# DressCode.net
KiCad netlist of a schematic drawn in EAGLE
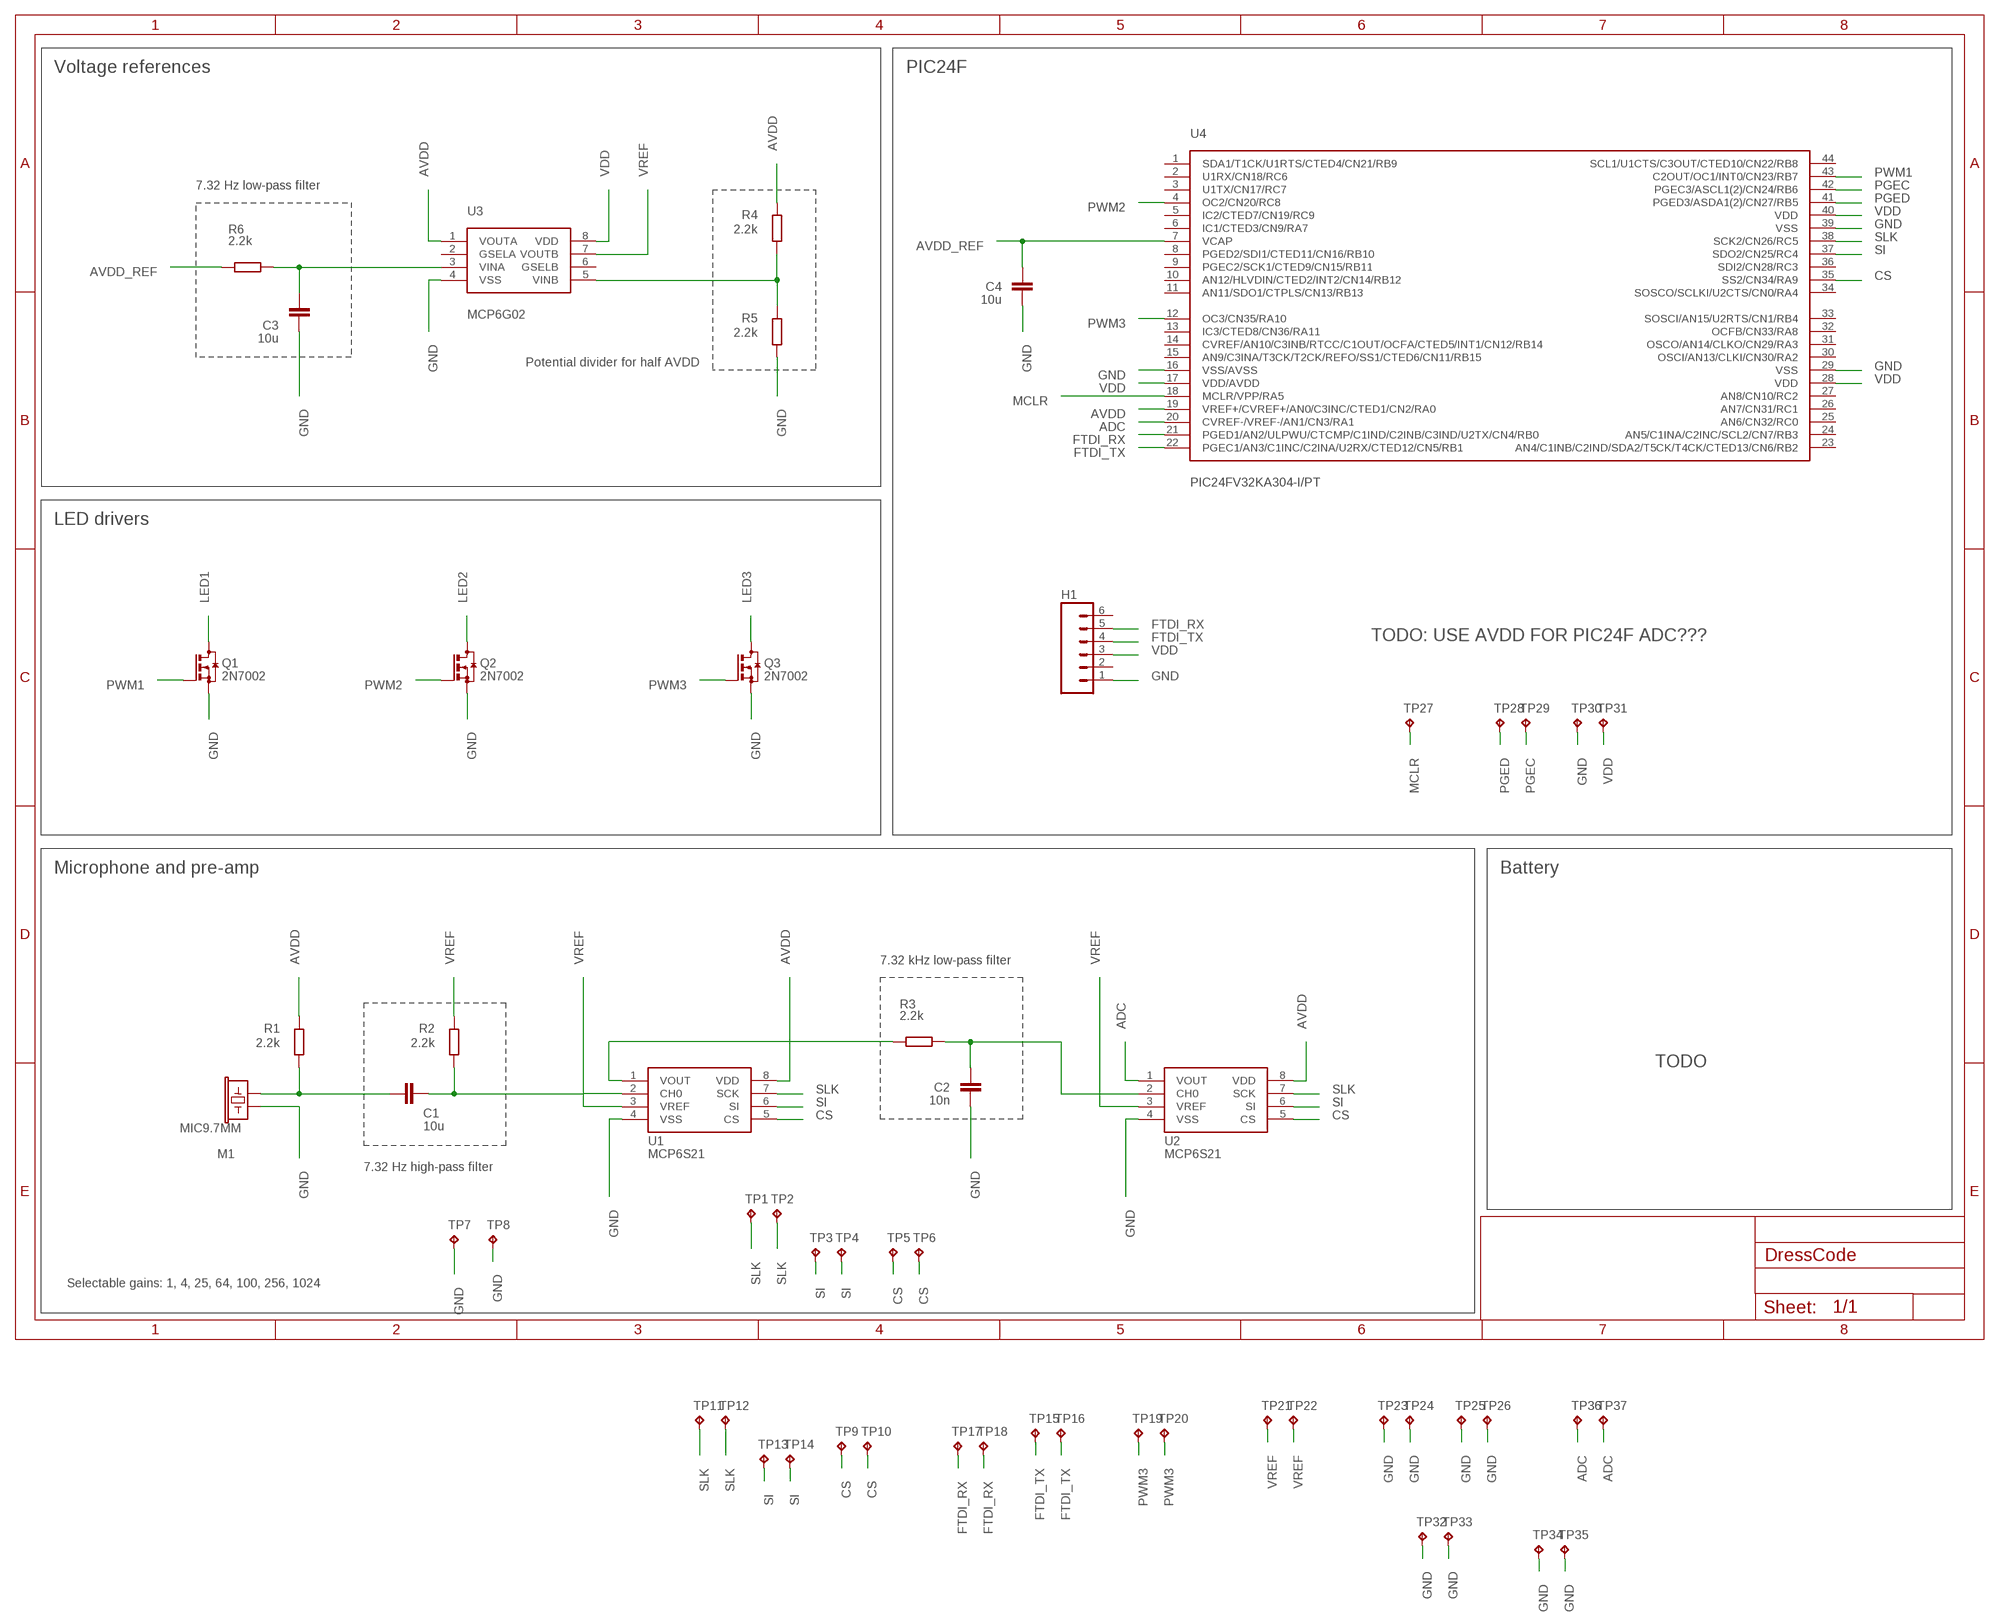
[diagram p0: schematic, sheet 1]

(export (version "E")
  (design (tool "Eeschema 10.0.6"))
  (components
    (comp (ref "C1")
      (value "10u")
      (footprint "eagle-import:C0805")
      (libsource (lib "eagle-import") (part "C-EUC0805"))
    )
    (comp (ref "C2")
      (value "10n")
      (footprint "eagle-import:C0805")
      (libsource (lib "eagle-import") (part "C-EUC0805"))
    )
    (comp (ref "C3")
      (value "10u")
      (footprint "eagle-import:C0805")
      (libsource (lib "eagle-import") (part "C-EUC0805"))
    )
    (comp (ref "C4")
      (value "10u")
      (footprint "eagle-import:C0805")
      (libsource (lib "eagle-import") (part "C-EUC0805"))
    )
    (comp (ref "H1")
      (value "M06LOCK")
      (footprint "eagle-import:1X06_LOCK")
      (libsource (lib "eagle-import") (part "M06LOCK"))
    )
    (comp (ref "M1")
      (value "MIC9.7MM")
      (footprint "eagle-import:MIC-9.7MM")
      (libsource (lib "eagle-import") (part "MIC9.7MM"))
    )
    (comp (ref "Q1")
      (value "2N7002")
      (footprint "eagle-import:SOT23")
      (libsource (lib "eagle-import") (part "BSS123"))
    )
    (comp (ref "Q2")
      (value "2N7002")
      (footprint "eagle-import:SOT23")
      (libsource (lib "eagle-import") (part "BSS123"))
    )
    (comp (ref "Q3")
      (value "2N7002")
      (footprint "eagle-import:SOT23")
      (libsource (lib "eagle-import") (part "BSS123"))
    )
    (comp (ref "R1")
      (value "2.2k")
      (footprint "eagle-import:R0805")
      (libsource (lib "eagle-import") (part "R-EU_R0805"))
    )
    (comp (ref "R2")
      (value "2.2k")
      (footprint "eagle-import:R0805")
      (libsource (lib "eagle-import") (part "R-EU_R0805"))
    )
    (comp (ref "R3")
      (value "2.2k")
      (footprint "eagle-import:R0805")
      (libsource (lib "eagle-import") (part "R-EU_R0805"))
    )
    (comp (ref "R4")
      (value "2.2k")
      (footprint "eagle-import:R0805")
      (libsource (lib "eagle-import") (part "R-EU_R0805"))
    )
    (comp (ref "R5")
      (value "2.2k")
      (footprint "eagle-import:R0805")
      (libsource (lib "eagle-import") (part "R-EU_R0805"))
    )
    (comp (ref "R6")
      (value "2.2k")
      (footprint "eagle-import:R0805")
      (libsource (lib "eagle-import") (part "R-EU_R0805"))
    )
    (comp (ref "TP1")
      (value "TPTP08R")
      (footprint "eagle-import:TP08R")
      (libsource (lib "eagle-import") (part "TPTP08R"))
    )
    (comp (ref "TP2")
      (value "TPTP08R")
      (footprint "eagle-import:TP08R")
      (libsource (lib "eagle-import") (part "TPTP08R"))
    )
    (comp (ref "TP3")
      (value "TPTP08R")
      (footprint "eagle-import:TP08R")
      (libsource (lib "eagle-import") (part "TPTP08R"))
    )
    (comp (ref "TP4")
      (value "TPTP08R")
      (footprint "eagle-import:TP08R")
      (libsource (lib "eagle-import") (part "TPTP08R"))
    )
    (comp (ref "TP5")
      (value "TPTP08R")
      (footprint "eagle-import:TP08R")
      (libsource (lib "eagle-import") (part "TPTP08R"))
    )
    (comp (ref "TP6")
      (value "TPTP08R")
      (footprint "eagle-import:TP08R")
      (libsource (lib "eagle-import") (part "TPTP08R"))
    )
    (comp (ref "TP7")
      (value "TPTP08R")
      (footprint "eagle-import:TP08R")
      (libsource (lib "eagle-import") (part "TPTP08R"))
    )
    (comp (ref "TP8")
      (value "TPTP08R")
      (footprint "eagle-import:TP08R")
      (libsource (lib "eagle-import") (part "TPTP08R"))
    )
    (comp (ref "TP9")
      (value "TPTP08R")
      (footprint "eagle-import:TP08R")
      (libsource (lib "eagle-import") (part "TPTP08R"))
    )
    (comp (ref "TP10")
      (value "TPTP08R")
      (footprint "eagle-import:TP08R")
      (libsource (lib "eagle-import") (part "TPTP08R"))
    )
    (comp (ref "TP11")
      (value "TPTP08R")
      (footprint "eagle-import:TP08R")
      (libsource (lib "eagle-import") (part "TPTP08R"))
    )
    (comp (ref "TP12")
      (value "TPTP08R")
      (footprint "eagle-import:TP08R")
      (libsource (lib "eagle-import") (part "TPTP08R"))
    )
    (comp (ref "TP13")
      (value "TPTP08R")
      (footprint "eagle-import:TP08R")
      (libsource (lib "eagle-import") (part "TPTP08R"))
    )
    (comp (ref "TP14")
      (value "TPTP08R")
      (footprint "eagle-import:TP08R")
      (libsource (lib "eagle-import") (part "TPTP08R"))
    )
    (comp (ref "TP15")
      (value "TPTP08R")
      (footprint "eagle-import:TP08R")
      (libsource (lib "eagle-import") (part "TPTP08R"))
    )
    (comp (ref "TP16")
      (value "TPTP08R")
      (footprint "eagle-import:TP08R")
      (libsource (lib "eagle-import") (part "TPTP08R"))
    )
    (comp (ref "TP17")
      (value "TPTP08R")
      (footprint "eagle-import:TP08R")
      (libsource (lib "eagle-import") (part "TPTP08R"))
    )
    (comp (ref "TP18")
      (value "TPTP08R")
      (footprint "eagle-import:TP08R")
      (libsource (lib "eagle-import") (part "TPTP08R"))
    )
    (comp (ref "TP19")
      (value "TPTP08R")
      (footprint "eagle-import:TP08R")
      (libsource (lib "eagle-import") (part "TPTP08R"))
    )
    (comp (ref "TP20")
      (value "TPTP08R")
      (footprint "eagle-import:TP08R")
      (libsource (lib "eagle-import") (part "TPTP08R"))
    )
    (comp (ref "TP21")
      (value "TPTP08R")
      (footprint "eagle-import:TP08R")
      (libsource (lib "eagle-import") (part "TPTP08R"))
    )
    (comp (ref "TP22")
      (value "TPTP08R")
      (footprint "eagle-import:TP08R")
      (libsource (lib "eagle-import") (part "TPTP08R"))
    )
    (comp (ref "TP23")
      (value "TPTP08R")
      (footprint "eagle-import:TP08R")
      (libsource (lib "eagle-import") (part "TPTP08R"))
    )
    (comp (ref "TP24")
      (value "TPTP08R")
      (footprint "eagle-import:TP08R")
      (libsource (lib "eagle-import") (part "TPTP08R"))
    )
    (comp (ref "TP25")
      (value "TPTP08R")
      (footprint "eagle-import:TP08R")
      (libsource (lib "eagle-import") (part "TPTP08R"))
    )
    (comp (ref "TP26")
      (value "TPTP08R")
      (footprint "eagle-import:TP08R")
      (libsource (lib "eagle-import") (part "TPTP08R"))
    )
    (comp (ref "TP27")
      (value "TPTP08R")
      (footprint "eagle-import:TP08R")
      (libsource (lib "eagle-import") (part "TPTP08R"))
    )
    (comp (ref "TP28")
      (value "TPTP08R")
      (footprint "eagle-import:TP08R")
      (libsource (lib "eagle-import") (part "TPTP08R"))
    )
    (comp (ref "TP29")
      (value "TPTP08R")
      (footprint "eagle-import:TP08R")
      (libsource (lib "eagle-import") (part "TPTP08R"))
    )
    (comp (ref "TP30")
      (value "TPTP08R")
      (footprint "eagle-import:TP08R")
      (libsource (lib "eagle-import") (part "TPTP08R"))
    )
    (comp (ref "TP31")
      (value "TPTP08R")
      (footprint "eagle-import:TP08R")
      (libsource (lib "eagle-import") (part "TPTP08R"))
    )
    (comp (ref "TP32")
      (value "TPTP08R")
      (footprint "eagle-import:TP08R")
      (libsource (lib "eagle-import") (part "TPTP08R"))
    )
    (comp (ref "TP33")
      (value "TPTP08R")
      (footprint "eagle-import:TP08R")
      (libsource (lib "eagle-import") (part "TPTP08R"))
    )
    (comp (ref "TP34")
      (value "TPTP08R")
      (footprint "eagle-import:TP08R")
      (libsource (lib "eagle-import") (part "TPTP08R"))
    )
    (comp (ref "TP35")
      (value "TPTP08R")
      (footprint "eagle-import:TP08R")
      (libsource (lib "eagle-import") (part "TPTP08R"))
    )
    (comp (ref "TP36")
      (value "TPTP08R")
      (footprint "eagle-import:TP08R")
      (libsource (lib "eagle-import") (part "TPTP08R"))
    )
    (comp (ref "TP37")
      (value "TPTP08R")
      (footprint "eagle-import:TP08R")
      (libsource (lib "eagle-import") (part "TPTP08R"))
    )
    (comp (ref "U1")
      (value "MCP6S21")
      (footprint "eagle-import:SOIC-8")
      (libsource (lib "eagle-import") (part "MCP6S21"))
    )
    (comp (ref "U2")
      (value "MCP6S21")
      (footprint "eagle-import:SOIC-8")
      (libsource (lib "eagle-import") (part "MCP6S21"))
    )
    (comp (ref "U3")
      (value "MCP6G02")
      (footprint "eagle-import:SOIC-8")
      (libsource (lib "eagle-import") (part "MCP6G02"))
    )
    (comp (ref "U4")
      (value "PIC24FV32KA304-I/PT")
      (footprint "eagle-import:TQFP44")
      (libsource (lib "eagle-import") (part "PIC24FV32KA304-I/PT"))
    )
  )
  (nets
    (net (code "1") (name "/ADC") (class "Default")
      (node (ref "TP36") (pin "TP") (pinfunction "TP_TP") (pintype "input"))
      (node (ref "TP37") (pin "TP") (pinfunction "TP_TP") (pintype "input"))
      (node (ref "U2") (pin "1") (pinfunction "VOUT_1") (pintype "bidirectional"))
      (node (ref "U4") (pin "20") (pinfunction "CVREF-/VREF-/AN1/CN3/RA1_20") (pintype "bidirectional"))
    )
    (net (code "2") (name "/AVDD") (class "Default")
      (node (ref "R1") (pin "2") (pinfunction "2_2") (pintype "passive"))
      (node (ref "R4") (pin "2") (pinfunction "2_2") (pintype "passive"))
      (node (ref "U1") (pin "8") (pinfunction "VDD_8") (pintype "bidirectional"))
      (node (ref "U2") (pin "8") (pinfunction "VDD_8") (pintype "bidirectional"))
      (node (ref "U3") (pin "1") (pinfunction "VOUTA_1") (pintype "bidirectional"))
      (node (ref "U4") (pin "19") (pinfunction "VREF+/CVREF+/AN0/C3INC/CTED1/CN2/RA0_19") (pintype "bidirectional"))
    )
    (net (code "3") (name "/AVDD_REF") (class "Default")
      (node (ref "C4") (pin "2") (pinfunction "2_2") (pintype "passive"))
      (node (ref "R6") (pin "1") (pinfunction "1_1") (pintype "passive"))
      (node (ref "U4") (pin "7") (pinfunction "VCAP_7") (pintype "bidirectional"))
    )
    (net (code "4") (name "/CS") (class "Default")
      (node (ref "TP10") (pin "TP") (pinfunction "TP_TP") (pintype "input"))
      (node (ref "TP5") (pin "TP") (pinfunction "TP_TP") (pintype "input"))
      (node (ref "TP6") (pin "TP") (pinfunction "TP_TP") (pintype "input"))
      (node (ref "TP9") (pin "TP") (pinfunction "TP_TP") (pintype "input"))
      (node (ref "U1") (pin "5") (pinfunction "CS_5") (pintype "bidirectional"))
      (node (ref "U2") (pin "5") (pinfunction "CS_5") (pintype "bidirectional"))
      (node (ref "U4") (pin "35") (pinfunction "SS2/CN34/RA9_35") (pintype "bidirectional"))
    )
    (net (code "5") (name "/FTDI_RX") (class "Default")
      (node (ref "H1") (pin "5") (pinfunction "5_5") (pintype "passive"))
      (node (ref "TP17") (pin "TP") (pinfunction "TP_TP") (pintype "input"))
      (node (ref "TP18") (pin "TP") (pinfunction "TP_TP") (pintype "input"))
      (node (ref "U4") (pin "21") (pinfunction "PGED1/AN2/ULPWU/CTCMP/C1IND/C2INB/C3IND/U2TX/CN4/RB0_21") (pintype "bidirectional"))
    )
    (net (code "6") (name "/FTDI_TX") (class "Default")
      (node (ref "H1") (pin "4") (pinfunction "4_4") (pintype "passive"))
      (node (ref "TP15") (pin "TP") (pinfunction "TP_TP") (pintype "input"))
      (node (ref "TP16") (pin "TP") (pinfunction "TP_TP") (pintype "input"))
      (node (ref "U4") (pin "22") (pinfunction "PGEC1/AN3/C1INC/C2INA/U2RX/CTED12/CN5/RB1_22") (pintype "bidirectional"))
    )
    (net (code "7") (name "/GND") (class "Default")
      (node (ref "C2") (pin "2") (pinfunction "2_2") (pintype "passive"))
      (node (ref "C3") (pin "1") (pinfunction "1_1") (pintype "passive"))
      (node (ref "C4") (pin "1") (pinfunction "1_1") (pintype "passive"))
      (node (ref "H1") (pin "1") (pinfunction "1_1") (pintype "passive"))
      (node (ref "M1") (pin "2") (pinfunction "2_2") (pintype "passive"))
      (node (ref "Q1") (pin "2") (pinfunction "S_2") (pintype "passive"))
      (node (ref "Q2") (pin "2") (pinfunction "S_2") (pintype "passive"))
      (node (ref "Q3") (pin "2") (pinfunction "S_2") (pintype "passive"))
      (node (ref "R5") (pin "1") (pinfunction "1_1") (pintype "passive"))
      (node (ref "TP23") (pin "TP") (pinfunction "TP_TP") (pintype "input"))
      (node (ref "TP24") (pin "TP") (pinfunction "TP_TP") (pintype "input"))
      (node (ref "TP25") (pin "TP") (pinfunction "TP_TP") (pintype "input"))
      (node (ref "TP26") (pin "TP") (pinfunction "TP_TP") (pintype "input"))
      (node (ref "TP30") (pin "TP") (pinfunction "TP_TP") (pintype "input"))
      (node (ref "TP32") (pin "TP") (pinfunction "TP_TP") (pintype "input"))
      (node (ref "TP33") (pin "TP") (pinfunction "TP_TP") (pintype "input"))
      (node (ref "TP34") (pin "TP") (pinfunction "TP_TP") (pintype "input"))
      (node (ref "TP35") (pin "TP") (pinfunction "TP_TP") (pintype "input"))
      (node (ref "TP7") (pin "TP") (pinfunction "TP_TP") (pintype "input"))
      (node (ref "TP8") (pin "TP") (pinfunction "TP_TP") (pintype "input"))
      (node (ref "U1") (pin "4") (pinfunction "VSS_4") (pintype "bidirectional"))
      (node (ref "U2") (pin "4") (pinfunction "VSS_4") (pintype "bidirectional"))
      (node (ref "U3") (pin "4") (pinfunction "VSS_4") (pintype "bidirectional"))
      (node (ref "U4") (pin "16") (pinfunction "VSS/AVSS_16") (pintype "bidirectional"))
      (node (ref "U4") (pin "29") (pinfunction "VSS_29") (pintype "bidirectional"))
      (node (ref "U4") (pin "39") (pinfunction "VSS_39") (pintype "bidirectional"))
    )
    (net (code "8") (name "/LED1") (class "Default")
      (node (ref "Q1") (pin "3") (pinfunction "D_3") (pintype "passive"))
    )
    (net (code "9") (name "/LED2") (class "Default")
      (node (ref "Q2") (pin "3") (pinfunction "D_3") (pintype "passive"))
    )
    (net (code "10") (name "/LED3") (class "Default")
      (node (ref "Q3") (pin "3") (pinfunction "D_3") (pintype "passive"))
    )
    (net (code "11") (name "/MCLR") (class "Default")
      (node (ref "TP27") (pin "TP") (pinfunction "TP_TP") (pintype "input"))
      (node (ref "U4") (pin "18") (pinfunction "MCLR/VPP/RA5_18") (pintype "bidirectional"))
    )
    (net (code "12") (name "/PGEC") (class "Default")
      (node (ref "TP29") (pin "TP") (pinfunction "TP_TP") (pintype "input"))
      (node (ref "U4") (pin "42") (pinfunction "PGEC3/ASCL1(2)/CN24/RB6_42") (pintype "bidirectional"))
    )
    (net (code "13") (name "/PGED") (class "Default")
      (node (ref "TP28") (pin "TP") (pinfunction "TP_TP") (pintype "input"))
      (node (ref "U4") (pin "41") (pinfunction "PGED3/ASDA1(2)/CN27/RB5_41") (pintype "bidirectional"))
    )
    (net (code "14") (name "/PWM1") (class "Default")
      (node (ref "Q1") (pin "1") (pinfunction "G_1") (pintype "passive"))
      (node (ref "U4") (pin "43") (pinfunction "C2OUT/OC1/INT0/CN23/RB7_43") (pintype "bidirectional"))
    )
    (net (code "15") (name "/PWM2") (class "Default")
      (node (ref "Q2") (pin "1") (pinfunction "G_1") (pintype "passive"))
      (node (ref "U4") (pin "4") (pinfunction "OC2/CN20/RC8_4") (pintype "bidirectional"))
    )
    (net (code "16") (name "/PWM3") (class "Default")
      (node (ref "Q3") (pin "1") (pinfunction "G_1") (pintype "passive"))
      (node (ref "TP19") (pin "TP") (pinfunction "TP_TP") (pintype "input"))
      (node (ref "TP20") (pin "TP") (pinfunction "TP_TP") (pintype "input"))
      (node (ref "U4") (pin "12") (pinfunction "OC3/CN35/RA10_12") (pintype "bidirectional"))
    )
    (net (code "17") (name "/SI") (class "Default")
      (node (ref "TP13") (pin "TP") (pinfunction "TP_TP") (pintype "input"))
      (node (ref "TP14") (pin "TP") (pinfunction "TP_TP") (pintype "input"))
      (node (ref "TP3") (pin "TP") (pinfunction "TP_TP") (pintype "input"))
      (node (ref "TP4") (pin "TP") (pinfunction "TP_TP") (pintype "input"))
      (node (ref "U1") (pin "6") (pinfunction "SI_6") (pintype "bidirectional"))
      (node (ref "U2") (pin "6") (pinfunction "SI_6") (pintype "bidirectional"))
      (node (ref "U4") (pin "37") (pinfunction "SDO2/CN25/RC4_37") (pintype "bidirectional"))
    )
    (net (code "18") (name "/SLK") (class "Default")
      (node (ref "TP1") (pin "TP") (pinfunction "TP_TP") (pintype "input"))
      (node (ref "TP11") (pin "TP") (pinfunction "TP_TP") (pintype "input"))
      (node (ref "TP12") (pin "TP") (pinfunction "TP_TP") (pintype "input"))
      (node (ref "TP2") (pin "TP") (pinfunction "TP_TP") (pintype "input"))
      (node (ref "U1") (pin "7") (pinfunction "SCK_7") (pintype "bidirectional"))
      (node (ref "U2") (pin "7") (pinfunction "SCK_7") (pintype "bidirectional"))
      (node (ref "U4") (pin "38") (pinfunction "SCK2/CN26/RC5_38") (pintype "bidirectional"))
    )
    (net (code "19") (name "/VDD") (class "Default")
      (node (ref "H1") (pin "3") (pinfunction "3_3") (pintype "passive"))
      (node (ref "TP31") (pin "TP") (pinfunction "TP_TP") (pintype "input"))
      (node (ref "U3") (pin "8") (pinfunction "VDD_8") (pintype "bidirectional"))
      (node (ref "U4") (pin "17") (pinfunction "VDD/AVDD_17") (pintype "bidirectional"))
      (node (ref "U4") (pin "28") (pinfunction "VDD_28") (pintype "bidirectional"))
      (node (ref "U4") (pin "40") (pinfunction "VDD_40") (pintype "bidirectional"))
    )
    (net (code "20") (name "/VREF") (class "Default")
      (node (ref "R2") (pin "2") (pinfunction "2_2") (pintype "passive"))
      (node (ref "TP21") (pin "TP") (pinfunction "TP_TP") (pintype "input"))
      (node (ref "TP22") (pin "TP") (pinfunction "TP_TP") (pintype "input"))
      (node (ref "U1") (pin "3") (pinfunction "VREF_3") (pintype "bidirectional"))
      (node (ref "U2") (pin "3") (pinfunction "VREF_3") (pintype "bidirectional"))
      (node (ref "U3") (pin "7") (pinfunction "VOUTB_7") (pintype "bidirectional"))
    )
    (net (code "21") (name "Net-(C1-Pad1)") (class "Default")
      (node (ref "C1") (pin "1") (pinfunction "1_1") (pintype "passive"))
      (node (ref "M1") (pin "1") (pinfunction "1_1") (pintype "passive"))
      (node (ref "R1") (pin "1") (pinfunction "1_1") (pintype "passive"))
    )
    (net (code "22") (name "Net-(U1-CH0)") (class "Default")
      (node (ref "C1") (pin "2") (pinfunction "2_2") (pintype "passive"))
      (node (ref "R2") (pin "1") (pinfunction "1_1") (pintype "passive"))
      (node (ref "U1") (pin "2") (pinfunction "CH0_2") (pintype "bidirectional"))
    )
    (net (code "23") (name "Net-(U1-VOUT)") (class "Default")
      (node (ref "R3") (pin "1") (pinfunction "1_1") (pintype "passive"))
      (node (ref "U1") (pin "1") (pinfunction "VOUT_1") (pintype "bidirectional"))
    )
    (net (code "24") (name "Net-(U2-CH0)") (class "Default")
      (node (ref "C2") (pin "1") (pinfunction "1_1") (pintype "passive"))
      (node (ref "R3") (pin "2") (pinfunction "2_2") (pintype "passive"))
      (node (ref "U2") (pin "2") (pinfunction "CH0_2") (pintype "bidirectional"))
    )
    (net (code "25") (name "Net-(U3-VINA)") (class "Default")
      (node (ref "C3") (pin "2") (pinfunction "2_2") (pintype "passive"))
      (node (ref "R6") (pin "2") (pinfunction "2_2") (pintype "passive"))
      (node (ref "U3") (pin "3") (pinfunction "VINA_3") (pintype "bidirectional"))
    )
    (net (code "26") (name "Net-(U3-VINB)") (class "Default")
      (node (ref "R4") (pin "1") (pinfunction "1_1") (pintype "passive"))
      (node (ref "R5") (pin "2") (pinfunction "2_2") (pintype "passive"))
      (node (ref "U3") (pin "5") (pinfunction "VINB_5") (pintype "bidirectional"))
    )
    (net (code "27") (name "unconnected-(H1-Pad2)") (class "Default")
      (node (ref "H1") (pin "2") (pinfunction "2_2") (pintype "passive"))
    )
    (net (code "28") (name "unconnected-(H1-Pad6)") (class "Default")
      (node (ref "H1") (pin "6") (pinfunction "6_6") (pintype "passive"))
    )
    (net (code "29") (name "unconnected-(U3-GSELA-Pad2)") (class "Default")
      (node (ref "U3") (pin "2") (pinfunction "GSELA_2") (pintype "bidirectional"))
    )
    (net (code "30") (name "unconnected-(U3-GSELB-Pad6)") (class "Default")
      (node (ref "U3") (pin "6") (pinfunction "GSELB_6") (pintype "bidirectional"))
    )
    (net (code "31") (name "unconnected-(U4-AN4{slash}C1INB{slash}C2IND{slash}SDA2{slash}T5CK{slash}T4CK{slash}CTED13{slash}CN6{slash}RB2-Pad23)") (class "Default")
      (node (ref "U4") (pin "23") (pinfunction "AN4/C1INB/C2IND/SDA2/T5CK/T4CK/CTED13/CN6/RB2_23") (pintype "bidirectional"))
    )
    (net (code "32") (name "unconnected-(U4-AN5{slash}C1INA{slash}C2INC{slash}SCL2{slash}CN7{slash}RB3-Pad24)") (class "Default")
      (node (ref "U4") (pin "24") (pinfunction "AN5/C1INA/C2INC/SCL2/CN7/RB3_24") (pintype "bidirectional"))
    )
    (net (code "33") (name "unconnected-(U4-AN6{slash}CN32{slash}RC0-Pad25)") (class "Default")
      (node (ref "U4") (pin "25") (pinfunction "AN6/CN32/RC0_25") (pintype "bidirectional"))
    )
    (net (code "34") (name "unconnected-(U4-AN7{slash}CN31{slash}RC1-Pad26)") (class "Default")
      (node (ref "U4") (pin "26") (pinfunction "AN7/CN31/RC1_26") (pintype "bidirectional"))
    )
    (net (code "35") (name "unconnected-(U4-AN8{slash}CN10{slash}RC2-Pad27)") (class "Default")
      (node (ref "U4") (pin "27") (pinfunction "AN8/CN10/RC2_27") (pintype "bidirectional"))
    )
    (net (code "36") (name "unconnected-(U4-AN9{slash}C3INA{slash}T3CK{slash}T2CK{slash}REFO{slash}SS1{slash}CTED6{slash}CN11{slash}RB15-Pad15)") (class "Default")
      (node (ref "U4") (pin "15") (pinfunction "AN9/C3INA/T3CK/T2CK/REFO/SS1/CTED6/CN11/RB15_15") (pintype "bidirectional"))
    )
    (net (code "37") (name "unconnected-(U4-AN11{slash}SDO1{slash}CTPLS{slash}CN13{slash}RB13-Pad11)") (class "Default")
      (node (ref "U4") (pin "11") (pinfunction "AN11/SDO1/CTPLS/CN13/RB13_11") (pintype "bidirectional"))
    )
    (net (code "38") (name "unconnected-(U4-AN12{slash}HLVDIN{slash}CTED2{slash}INT2{slash}CN14{slash}RB12-Pad10)") (class "Default")
      (node (ref "U4") (pin "10") (pinfunction "AN12/HLVDIN/CTED2/INT2/CN14/RB12_10") (pintype "bidirectional"))
    )
    (net (code "39") (name "unconnected-(U4-CVREF{slash}AN10{slash}C3INB{slash}RTCC{slash}C1OUT{slash}OCFA{slash}CTED5{slash}INT1{slash}CN12{slash}RB14-Pad14)") (class "Default")
      (node (ref "U4") (pin "14") (pinfunction "CVREF/AN10/C3INB/RTCC/C1OUT/OCFA/CTED5/INT1/CN12/RB14_14") (pintype "bidirectional"))
    )
    (net (code "40") (name "unconnected-(U4-IC1{slash}CTED3{slash}CN9{slash}RA7-Pad6)") (class "Default")
      (node (ref "U4") (pin "6") (pinfunction "IC1/CTED3/CN9/RA7_6") (pintype "bidirectional"))
    )
    (net (code "41") (name "unconnected-(U4-IC2{slash}CTED7{slash}CN19{slash}RC9-Pad5)") (class "Default")
      (node (ref "U4") (pin "5") (pinfunction "IC2/CTED7/CN19/RC9_5") (pintype "bidirectional"))
    )
    (net (code "42") (name "unconnected-(U4-IC3{slash}CTED8{slash}CN36{slash}RA11-Pad13)") (class "Default")
      (node (ref "U4") (pin "13") (pinfunction "IC3/CTED8/CN36/RA11_13") (pintype "bidirectional"))
    )
    (net (code "43") (name "unconnected-(U4-OCFB{slash}CN33{slash}RA8-Pad32)") (class "Default")
      (node (ref "U4") (pin "32") (pinfunction "OCFB/CN33/RA8_32") (pintype "bidirectional"))
    )
    (net (code "44") (name "unconnected-(U4-OSCI{slash}AN13{slash}CLKI{slash}CN30{slash}RA2-Pad30)") (class "Default")
      (node (ref "U4") (pin "30") (pinfunction "OSCI/AN13/CLKI/CN30/RA2_30") (pintype "bidirectional"))
    )
    (net (code "45") (name "unconnected-(U4-OSCO{slash}AN14{slash}CLKO{slash}CN29{slash}RA3-Pad31)") (class "Default")
      (node (ref "U4") (pin "31") (pinfunction "OSCO/AN14/CLKO/CN29/RA3_31") (pintype "bidirectional"))
    )
    (net (code "46") (name "unconnected-(U4-PGEC2{slash}SCK1{slash}CTED9{slash}CN15{slash}RB11-Pad9)") (class "Default")
      (node (ref "U4") (pin "9") (pinfunction "PGEC2/SCK1/CTED9/CN15/RB11_9") (pintype "bidirectional"))
    )
    (net (code "47") (name "unconnected-(U4-PGED2{slash}SDI1{slash}CTED11{slash}CN16{slash}RB10-Pad8)") (class "Default")
      (node (ref "U4") (pin "8") (pinfunction "PGED2/SDI1/CTED11/CN16/RB10_8") (pintype "bidirectional"))
    )
    (net (code "48") (name "unconnected-(U4-SCL1{slash}U1CTS{slash}C3OUT{slash}CTED10{slash}CN22{slash}RB8-Pad44)") (class "Default")
      (node (ref "U4") (pin "44") (pinfunction "SCL1/U1CTS/C3OUT/CTED10/CN22/RB8_44") (pintype "bidirectional"))
    )
    (net (code "49") (name "unconnected-(U4-SDA1{slash}T1CK{slash}U1RTS{slash}CTED4{slash}CN21{slash}RB9-Pad1)") (class "Default")
      (node (ref "U4") (pin "1") (pinfunction "SDA1/T1CK/U1RTS/CTED4/CN21/RB9_1") (pintype "bidirectional"))
    )
    (net (code "50") (name "unconnected-(U4-SDI2{slash}CN28{slash}RC3-Pad36)") (class "Default")
      (node (ref "U4") (pin "36") (pinfunction "SDI2/CN28/RC3_36") (pintype "bidirectional"))
    )
    (net (code "51") (name "unconnected-(U4-SOSCI{slash}AN15{slash}U2RTS{slash}CN1{slash}RB4-Pad33)") (class "Default")
      (node (ref "U4") (pin "33") (pinfunction "SOSCI/AN15/U2RTS/CN1/RB4_33") (pintype "bidirectional"))
    )
    (net (code "52") (name "unconnected-(U4-SOSCO{slash}SCLKI{slash}U2CTS{slash}CN0{slash}RA4-Pad34)") (class "Default")
      (node (ref "U4") (pin "34") (pinfunction "SOSCO/SCLKI/U2CTS/CN0/RA4_34") (pintype "bidirectional"))
    )
    (net (code "53") (name "unconnected-(U4-U1RX{slash}CN18{slash}RC6-Pad2)") (class "Default")
      (node (ref "U4") (pin "2") (pinfunction "U1RX/CN18/RC6_2") (pintype "bidirectional"))
    )
    (net (code "54") (name "unconnected-(U4-U1TX{slash}CN17{slash}RC7-Pad3)") (class "Default")
      (node (ref "U4") (pin "3") (pinfunction "U1TX/CN17/RC7_3") (pintype "bidirectional"))
    )
  )
)
